# Power_12V_Rev1_1.net
KiCad netlist of a schematic drawn in Altium Designer
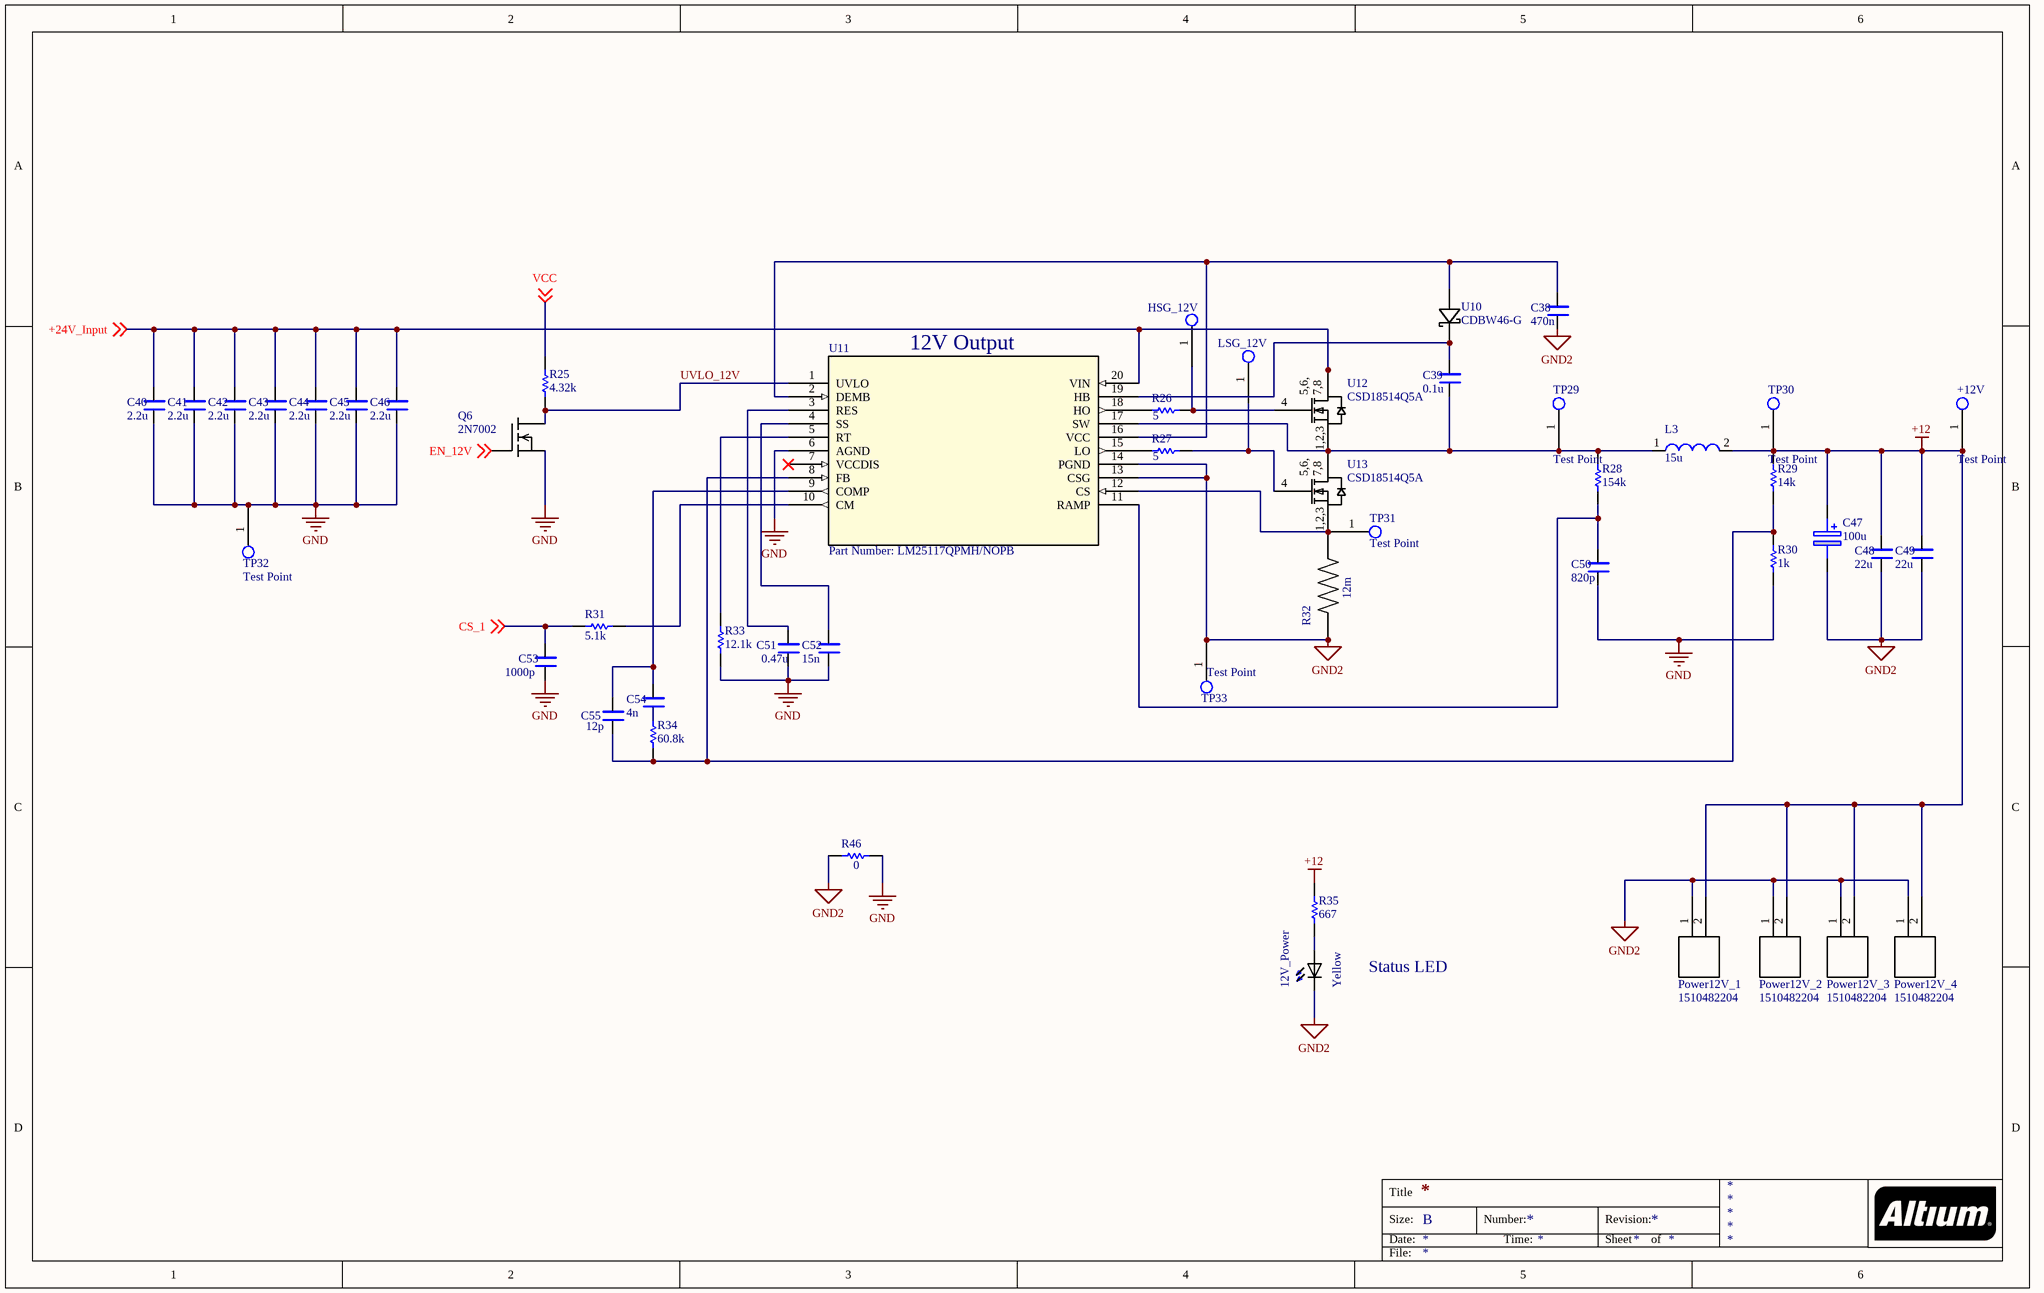
[diagram p0: Power_12V_Rev1.1.SchDoc]

(export (version "E")
  (design (tool "Eeschema 10.0.6"))
  (components
    (comp (ref "+12V")
      (value "Test Point")
      (footprint "Test Point Through-hole")
      (libsource (lib "Test Points") (part "Test Point"))
    )
    (comp (ref "12V_Power")
      (value "Yellow")
      (footprint "*DIOC200X125X110_LTST-C171KSKT(Primary)")
      (description "Yellow 2 x 1.25 x 0.8 mm 130Â° Water Clear 50 mcd 2 V LED SMT")
      (fields (field (name "MP") "LTST-C171KSKT") (field (name "DIGI-KEY_PART_NUMBER") "160-1428-1-ND"))
      (libsource (lib "LTST-C171KSKT") (part "LTST-C171KSKT"))
    )
    (comp (ref "C38")
      (value "470n")
      (footprint "*CAPC2012X88N")
      (description "100pF Â±5% 250V Ceramic Capacitor C0G, NP0 0805 _2012 Metric_")
      (fields (field (name "MF") "KEMET") (field (name "DIGI-KEY_PART_NUMBER") "399-15000-1-ND"))
      (libsource (lib "C0805C101JAGAC7800") (part "C0805C101JAGAC7800"))
    )
    (comp (ref "C39")
      (value "0.1u")
      (footprint "*CAPC2012X88N")
      (description "100pF Â±5% 250V Ceramic Capacitor C0G, NP0 0805 _2012 Metric_")
      (fields (field (name "MF") "KEMET") (field (name "DIGI-KEY_PART_NUMBER") "399-15000-1-ND"))
      (libsource (lib "C0805C101JAGAC7800") (part "C0805C101JAGAC7800"))
    )
    (comp (ref "C40")
      (value "2.2u")
      (footprint "*CAPC2012X88N")
      (description "100pF Â±5% 250V Ceramic Capacitor C0G, NP0 0805 _2012 Metric_")
      (fields (field (name "MF") "KEMET") (field (name "DIGI-KEY_PART_NUMBER") "399-15000-1-ND"))
      (libsource (lib "C0805C101JAGAC7800") (part "C0805C101JAGAC7800"))
    )
    (comp (ref "C41")
      (value "2.2u")
      (footprint "*CAPC2012X88N")
      (description "100pF Â±5% 250V Ceramic Capacitor C0G, NP0 0805 _2012 Metric_")
      (fields (field (name "MF") "KEMET") (field (name "DIGI-KEY_PART_NUMBER") "399-15000-1-ND"))
      (libsource (lib "C0805C101JAGAC7800") (part "C0805C101JAGAC7800"))
    )
    (comp (ref "C42")
      (value "2.2u")
      (footprint "*CAPC2012X88N")
      (description "100pF Â±5% 250V Ceramic Capacitor C0G, NP0 0805 _2012 Metric_")
      (fields (field (name "MF") "KEMET") (field (name "DIGI-KEY_PART_NUMBER") "399-15000-1-ND"))
      (libsource (lib "C0805C101JAGAC7800") (part "C0805C101JAGAC7800"))
    )
    (comp (ref "C43")
      (value "2.2u")
      (footprint "*CAPC2012X88N")
      (description "100pF Â±5% 250V Ceramic Capacitor C0G, NP0 0805 _2012 Metric_")
      (fields (field (name "MF") "KEMET") (field (name "DIGI-KEY_PART_NUMBER") "399-15000-1-ND"))
      (libsource (lib "C0805C101JAGAC7800") (part "C0805C101JAGAC7800"))
    )
    (comp (ref "C44")
      (value "2.2u")
      (footprint "*CAPC2012X88N")
      (description "100pF Â±5% 250V Ceramic Capacitor C0G, NP0 0805 _2012 Metric_")
      (fields (field (name "MF") "KEMET") (field (name "DIGI-KEY_PART_NUMBER") "399-15000-1-ND"))
      (libsource (lib "C0805C101JAGAC7800") (part "C0805C101JAGAC7800"))
    )
    (comp (ref "C45")
      (value "2.2u")
      (footprint "*CAPC2012X88N")
      (description "100pF Â±5% 250V Ceramic Capacitor C0G, NP0 0805 _2012 Metric_")
      (fields (field (name "MF") "KEMET") (field (name "DIGI-KEY_PART_NUMBER") "399-15000-1-ND"))
      (libsource (lib "C0805C101JAGAC7800") (part "C0805C101JAGAC7800"))
    )
    (comp (ref "C46")
      (value "2.2u")
      (footprint "*CAPC2012X88N")
      (description "100pF Â±5% 250V Ceramic Capacitor C0G, NP0 0805 _2012 Metric_")
      (fields (field (name "MF") "KEMET") (field (name "DIGI-KEY_PART_NUMBER") "399-15000-1-ND"))
      (libsource (lib "C0805C101JAGAC7800") (part "C0805C101JAGAC7800"))
    )
    (comp (ref "C47")
      (value "100u")
      (footprint "CAPPRD500W65D1000H1800")
      (fields
        (field (name "MANUFACTURER_PART_NUMBER") "EEUFC1V331")
        (field (name "RS PART NUMBER") "1081337")
      )
      (libsource (lib "Power Distribution") (part "EEUFC1V331"))
    )
    (comp (ref "C48")
      (value "22u")
      (footprint "*CAPC2012X88N")
      (description "100pF Â±5% 250V Ceramic Capacitor C0G, NP0 0805 _2012 Metric_")
      (fields (field (name "MF") "KEMET") (field (name "DIGI-KEY_PART_NUMBER") "399-15000-1-ND"))
      (libsource (lib "C0805C101JAGAC7800") (part "C0805C101JAGAC7800"))
    )
    (comp (ref "C49")
      (value "22u")
      (footprint "*CAPC2012X88N")
      (description "100pF Â±5% 250V Ceramic Capacitor C0G, NP0 0805 _2012 Metric_")
      (fields (field (name "MF") "KEMET") (field (name "DIGI-KEY_PART_NUMBER") "399-15000-1-ND"))
      (libsource (lib "C0805C101JAGAC7800") (part "C0805C101JAGAC7800"))
    )
    (comp (ref "C50")
      (value "820p")
      (footprint "*CAPC2012X88N")
      (description "100pF Â±5% 250V Ceramic Capacitor C0G, NP0 0805 _2012 Metric_")
      (fields (field (name "MF") "KEMET") (field (name "DIGI-KEY_PART_NUMBER") "399-15000-1-ND"))
      (libsource (lib "C0805C101JAGAC7800") (part "C0805C101JAGAC7800"))
    )
    (comp (ref "C51")
      (value "0.47u")
      (footprint "*CAPC2012X88N")
      (description "100pF Â±5% 250V Ceramic Capacitor C0G, NP0 0805 _2012 Metric_")
      (fields (field (name "MF") "KEMET") (field (name "DIGI-KEY_PART_NUMBER") "399-15000-1-ND"))
      (libsource (lib "C0805C101JAGAC7800") (part "C0805C101JAGAC7800"))
    )
    (comp (ref "C52")
      (value "15n")
      (footprint "*CAPC2012X88N")
      (description "100pF Â±5% 250V Ceramic Capacitor C0G, NP0 0805 _2012 Metric_")
      (fields (field (name "MF") "KEMET") (field (name "DIGI-KEY_PART_NUMBER") "399-15000-1-ND"))
      (libsource (lib "C0805C101JAGAC7800") (part "C0805C101JAGAC7800"))
    )
    (comp (ref "C53")
      (value "1000p")
      (footprint "*CAPC2012X88N")
      (description "100pF Â±5% 250V Ceramic Capacitor C0G, NP0 0805 _2012 Metric_")
      (fields (field (name "MF") "KEMET") (field (name "DIGI-KEY_PART_NUMBER") "399-15000-1-ND"))
      (libsource (lib "C0805C101JAGAC7800") (part "C0805C101JAGAC7800"))
    )
    (comp (ref "C54")
      (value "4n")
      (footprint "*CAPC2012X88N")
      (description "100pF Â±5% 250V Ceramic Capacitor C0G, NP0 0805 _2012 Metric_")
      (fields (field (name "MF") "KEMET") (field (name "DIGI-KEY_PART_NUMBER") "399-15000-1-ND"))
      (libsource (lib "C0805C101JAGAC7800") (part "C0805C101JAGAC7800"))
    )
    (comp (ref "C55")
      (value "12p")
      (footprint "*CAPC2012X88N")
      (description "100pF Â±5% 250V Ceramic Capacitor C0G, NP0 0805 _2012 Metric_")
      (fields (field (name "MF") "KEMET") (field (name "DIGI-KEY_PART_NUMBER") "399-15000-1-ND"))
      (libsource (lib "C0805C101JAGAC7800") (part "C0805C101JAGAC7800"))
    )
    (comp (ref "HSG_12V")
      (value "~")
      (footprint "Test Point Through-hole")
      (libsource (lib "Test Points") (part "Test Point"))
    )
    (comp (ref "L3")
      (value "15u")
      (footprint "XAL1010-682")
      (description "Power inductor, high current, 10% tol, SMT, RoHS")
      (fields (field (name "MF") "Coilcraft") (field (name "MP") "SER2915H-153KL"))
      (libsource (lib "SER2915H-153KL") (part "SER2915H-153KL"))
    )
    (comp (ref "LSG_12V")
      (value "~")
      (footprint "Test Point Through-hole")
      (libsource (lib "Test Points") (part "Test Point"))
    )
    (comp (ref "Power12V_1")
      (value "1510482204")
      (footprint "1510482204")
      (description "Molex 6.5MM 2 pin connector, used for power connections. P/N 1510482204 and similar models.")
      (libsource (lib "Power Distribution") (part "1510482204"))
    )
    (comp (ref "Power12V_2")
      (value "1510482204")
      (footprint "1510482204")
      (description "Molex 6.5MM 2 pin connector, used for power connections. P/N 1510482204 and similar models.")
      (libsource (lib "Power Distribution") (part "1510482204"))
    )
    (comp (ref "Power12V_3")
      (value "1510482204")
      (footprint "1510482204")
      (description "Molex 6.5MM 2 pin connector, used for power connections. P/N 1510482204 and similar models.")
      (libsource (lib "Power Distribution") (part "1510482204"))
    )
    (comp (ref "Power12V_4")
      (value "1510482204")
      (footprint "1510482204")
      (description "Molex 6.5MM 2 pin connector, used for power connections. P/N 1510482204 and similar models.")
      (libsource (lib "Power Distribution") (part "1510482204"))
    )
    (comp (ref "Q6")
      (value "2N7002")
      (footprint "*SOT23")
      (description "Trans MOSFET N-CH 60V 0.115A 3-Pin SOT-23 T/R")
      (fields (field (name "MF") "ON Semiconductor"))
      (libsource (lib "2N7002") (part "2N7002"))
    )
    (comp (ref "R25")
      (value "4.32k")
      (footprint "RESC0805(2012)_M")
      (description "8M06 0.125W 1% 0805 (2012 Metric)  SMD")
      (fields (field (name "POWER") "0.125 W") (field (name "TOLERANCE") "1 %"))
      (libsource (lib "Altium Content Vault") (part "RES"))
    )
    (comp (ref "R26")
      (value "5")
      (footprint "AXIAL-0.3")
      (description "120R 0.125W 5% 0805 (2012 Metric)  SMD")
      (fields (field (name "TOLERANCE") "5 %") (field (name "POWER") "0.125 W"))
      (libsource (lib "Power Distribution") (part "120R 5% 0805"))
    )
    (comp (ref "R27")
      (value "5")
      (footprint "AXIAL-0.3")
      (description "120R 0.125W 5% 0805 (2012 Metric)  SMD")
      (fields (field (name "TOLERANCE") "5 %") (field (name "POWER") "0.125 W"))
      (libsource (lib "Power Distribution") (part "120R 5% 0805"))
    )
    (comp (ref "R28")
      (value "154k")
      (footprint "RESC0805(2012)_M")
      (description "8M06 0.125W 1% 0805 (2012 Metric)  SMD")
      (fields (field (name "POWER") "0.125 W") (field (name "TOLERANCE") "1 %"))
      (libsource (lib "Altium Content Vault") (part "RES"))
    )
    (comp (ref "R29")
      (value "14k")
      (footprint "RESC0805(2012)_M")
      (description "8M06 0.125W 1% 0805 (2012 Metric)  SMD")
      (fields (field (name "POWER") "0.125 W") (field (name "TOLERANCE") "1 %"))
      (libsource (lib "Altium Content Vault") (part "RES"))
    )
    (comp (ref "R30")
      (value "1k")
      (footprint "RESC0805(2012)_M")
      (description "8M06 0.125W 1% 0805 (2012 Metric)  SMD")
      (fields (field (name "POWER") "0.125 W") (field (name "TOLERANCE") "1 %"))
      (libsource (lib "Altium Content Vault") (part "RES"))
    )
    (comp (ref "R31")
      (value "5.1k")
      (footprint "RESC0805(2012)_M")
      (description "8M06 0.125W 1% 0805 (2012 Metric)  SMD")
      (fields (field (name "POWER") "0.125 W") (field (name "TOLERANCE") "1 %"))
      (libsource (lib "Altium Content Vault") (part "RES"))
    )
    (comp (ref "R32")
      (value "12m")
      (footprint "*RESC6432X110N")
      (description "Res Thick Film 2512 0.012 Ohm 1% 1W Pad SMD Automotive T/R")
      (fields (field (name "MP") "ERJ-M1WSF12MU") (field (name "DIGI-KEY_PART_NUMBER") "P12MCT-ND"))
      (libsource (lib "ERJ-M1WSF12MU") (part "ERJ-M1WSF12MU"))
    )
    (comp (ref "R33")
      (value "12.1k")
      (footprint "RESC0805(2012)_M")
      (description "8M06 0.125W 1% 0805 (2012 Metric)  SMD")
      (fields (field (name "POWER") "0.125 W") (field (name "TOLERANCE") "1 %"))
      (libsource (lib "Altium Content Vault") (part "RES"))
    )
    (comp (ref "R34")
      (value "60.8k")
      (footprint "RESC0805(2012)_M")
      (description "8M06 0.125W 1% 0805 (2012 Metric)  SMD")
      (fields (field (name "POWER") "0.125 W") (field (name "TOLERANCE") "1 %"))
      (libsource (lib "Altium Content Vault") (part "RES"))
    )
    (comp (ref "R35")
      (value "667")
      (footprint "RESC0805(2012)_M")
      (description "8M06 0.125W 1% 0805 (2012 Metric)  SMD")
      (fields (field (name "POWER") "0.125 W") (field (name "TOLERANCE") "1 %"))
      (libsource (lib "Altium Content Vault") (part "RES"))
    )
    (comp (ref "R46")
      (value "0")
      (footprint "RESC0805(2012)_M")
      (description "8M06 0.125W 1% 0805 (2012 Metric)  SMD")
      (fields (field (name "POWER") "0.125 W") (field (name "TOLERANCE") "1 %"))
      (libsource (lib "Altium Content Vault") (part "RES"))
    )
    (comp (ref "TP29")
      (value "Test Point")
      (footprint "Test Point Through-hole")
      (libsource (lib "Test Points") (part "Test Point"))
    )
    (comp (ref "TP30")
      (value "Test Point")
      (footprint "Test Point Through-hole")
      (libsource (lib "Test Points") (part "Test Point"))
    )
    (comp (ref "TP31")
      (value "Test Point")
      (footprint "Test Point Through-hole")
      (libsource (lib "Test Points") (part "Test Point"))
    )
    (comp (ref "TP32")
      (value "Test Point")
      (footprint "Test Point Through-hole")
      (libsource (lib "Test Points") (part "Test Point"))
    )
    (comp (ref "TP33")
      (value "Test Point")
      (footprint "Test Point Through-hole")
      (libsource (lib "Test Points") (part "Test Point"))
    )
    (comp (ref "U10")
      (value "CDBW46-G")
      (footprint "CDBW")
      (description "No Description Available")
      (fields (field (name "COPYRIGHT") "Copyright (C) 2018 Accelerated Designs. All rights reserved"))
      (libsource (lib "DIODE SCHOTTKY 100V 150MA") (part "CDBW46-G"))
    )
    (comp (ref "U11")
      (value "Part Number: LM25117QPMH/NOPB")
      (footprint "MXA20A")
      (description "No Description Available")
      (fields
        (field (name "MANUFACTURER") "Texas Instruments")
        (field (name "MANUFACTURER_PART_NUMBER") "LM25117QPMH/NOPB")
        (field (name "COPYRIGHT") "Copyright (C) 2018 Accelerated Designs. All rights reserved")
      )
      (libsource (lib "2019-11-16_22-35-15") (part "LM25117QPMH/NOPB"))
    )
    (comp (ref "U12")
      (value "CSD18514Q5A")
      (footprint "DQJ0008A")
      (description "No Description Available")
      (fields (field (name "COPYRIGHT") "Copyright (C) 2018 Accelerated Designs. All rights reserved"))
      (libsource (lib "ul_CSD18514Q5A") (part "CSD18514Q5A"))
    )
    (comp (ref "U13")
      (value "CSD18514Q5A")
      (footprint "DQJ0008A")
      (description "No Description Available")
      (fields (field (name "COPYRIGHT") "Copyright (C) 2018 Accelerated Designs. All rights reserved"))
      (libsource (lib "ul_CSD18514Q5A") (part "CSD18514Q5A"))
    )
  )
  (nets
    (net (code "1") (name "+12") (class "Default")
      (node (ref "+12V") (pin "1") (pinfunction "1_1") (pintype "passive"))
      (node (ref "C47") (pin "1") (pinfunction "+_1") (pintype "passive"))
      (node (ref "C48") (pin "2") (pinfunction "2_2") (pintype "passive"))
      (node (ref "C49") (pin "2") (pinfunction "2_2") (pintype "passive"))
      (node (ref "L3") (pin "2") (pinfunction "2_2") (pintype "passive"))
      (node (ref "Power12V_1") (pin "2") (pintype "passive"))
      (node (ref "Power12V_2") (pin "2") (pintype "passive"))
      (node (ref "Power12V_3") (pin "2") (pintype "passive"))
      (node (ref "Power12V_4") (pin "2") (pintype "passive"))
      (node (ref "R29") (pin "2") (pinfunction "2_2") (pintype "passive"))
      (node (ref "R35") (pin "2") (pinfunction "2_2") (pintype "passive"))
      (node (ref "TP30") (pin "1") (pinfunction "1_1") (pintype "passive"))
    )
    (net (code "2") (name "+24V_Input") (class "Default")
      (node (ref "C40") (pin "2") (pinfunction "2_2") (pintype "passive"))
      (node (ref "C41") (pin "2") (pinfunction "2_2") (pintype "passive"))
      (node (ref "C42") (pin "2") (pinfunction "2_2") (pintype "passive"))
      (node (ref "C43") (pin "2") (pinfunction "2_2") (pintype "passive"))
      (node (ref "C44") (pin "2") (pinfunction "2_2") (pintype "passive"))
      (node (ref "C45") (pin "2") (pinfunction "2_2") (pintype "passive"))
      (node (ref "C46") (pin "2") (pinfunction "2_2") (pintype "passive"))
      (node (ref "U11") (pin "20") (pinfunction "VIN_20") (pintype "input"))
      (node (ref "U12") (pin "5") (pinfunction "D_5") (pintype "passive"))
      (node (ref "U12") (pin "6") (pinfunction "D_6") (pintype "passive"))
      (node (ref "U12") (pin "7") (pinfunction "D_7") (pintype "passive"))
      (node (ref "U12") (pin "8") (pinfunction "D_8") (pintype "passive"))
    )
    (net (code "3") (name "/UVLO_12V") (class "Default")
      (node (ref "Q6") (pin "3") (pinfunction "D_3") (pintype "passive"))
      (node (ref "R25") (pin "1") (pinfunction "1_1") (pintype "passive"))
      (node (ref "U11") (pin "1") (pinfunction "UVLO_1") (pintype "passive"))
    )
    (net (code "4") (name "CS_1") (class "Default")
      (node (ref "C53") (pin "2") (pinfunction "2_2") (pintype "passive"))
      (node (ref "R31") (pin "2") (pinfunction "2_2") (pintype "passive"))
    )
    (net (code "5") (name "EN_12V") (class "Default")
      (node (ref "Q6") (pin "1") (pinfunction "G_1") (pintype "passive"))
    )
    (net (code "6") (name "GND") (class "Default")
      (node (ref "C40") (pin "1") (pinfunction "1_1") (pintype "passive"))
      (node (ref "C41") (pin "1") (pinfunction "1_1") (pintype "passive"))
      (node (ref "C42") (pin "1") (pinfunction "1_1") (pintype "passive"))
      (node (ref "C43") (pin "1") (pinfunction "1_1") (pintype "passive"))
      (node (ref "C44") (pin "1") (pinfunction "1_1") (pintype "passive"))
      (node (ref "C45") (pin "1") (pinfunction "1_1") (pintype "passive"))
      (node (ref "C46") (pin "1") (pinfunction "1_1") (pintype "passive"))
      (node (ref "C50") (pin "1") (pinfunction "1_1") (pintype "passive"))
      (node (ref "C51") (pin "1") (pinfunction "1_1") (pintype "passive"))
      (node (ref "C52") (pin "1") (pinfunction "1_1") (pintype "passive"))
      (node (ref "C53") (pin "1") (pinfunction "1_1") (pintype "passive"))
      (node (ref "Q6") (pin "2") (pinfunction "S_2") (pintype "passive"))
      (node (ref "R30") (pin "1") (pinfunction "1_1") (pintype "passive"))
      (node (ref "R33") (pin "1") (pinfunction "1_1") (pintype "passive"))
      (node (ref "R46") (pin "1") (pinfunction "1_1") (pintype "passive"))
      (node (ref "TP32") (pin "1") (pinfunction "1_1") (pintype "passive"))
      (node (ref "U11") (pin "6") (pinfunction "AGND_6") (pintype "power_in"))
    )
    (net (code "7") (name "GND2") (class "Default")
      (node (ref "12V_Power") (pin "NEG") (pinfunction "NEG_NEG") (pintype "passive"))
      (node (ref "C38") (pin "1") (pinfunction "1_1") (pintype "passive"))
      (node (ref "C47") (pin "2") (pinfunction "-_2") (pintype "passive"))
      (node (ref "C48") (pin "1") (pinfunction "1_1") (pintype "passive"))
      (node (ref "C49") (pin "1") (pinfunction "1_1") (pintype "passive"))
      (node (ref "Power12V_1") (pin "1") (pintype "passive"))
      (node (ref "Power12V_2") (pin "1") (pintype "passive"))
      (node (ref "Power12V_3") (pin "1") (pintype "passive"))
      (node (ref "Power12V_4") (pin "1") (pintype "passive"))
      (node (ref "R32") (pin "1") (pinfunction "1_1") (pintype "passive"))
      (node (ref "R46") (pin "2") (pinfunction "2_2") (pintype "passive"))
      (node (ref "TP33") (pin "1") (pinfunction "1_1") (pintype "passive"))
      (node (ref "U11") (pin "13") (pinfunction "CSG_13") (pintype "passive"))
      (node (ref "U11") (pin "14") (pinfunction "PGND_14") (pintype "power_in"))
    )
    (net (code "8") (name "Net-(12V_Power-PadPOS)") (class "Default")
      (node (ref "12V_Power") (pin "POS") (pinfunction "POS_POS") (pintype "passive"))
      (node (ref "R35") (pin "1") (pinfunction "1_1") (pintype "passive"))
    )
    (net (code "9") (name "Net-(C54-Pad1)") (class "Default")
      (node (ref "C54") (pin "1") (pinfunction "1_1") (pintype "passive"))
      (node (ref "R34") (pin "2") (pinfunction "2_2") (pintype "passive"))
    )
    (net (code "10") (name "Net-(U11-CM)") (class "Default")
      (node (ref "R31") (pin "1") (pinfunction "1_1") (pintype "passive"))
      (node (ref "U11") (pin "10") (pinfunction "CM_10") (pintype "output"))
    )
    (net (code "11") (name "Net-(U11-COMP)") (class "Default")
      (node (ref "C54") (pin "2") (pinfunction "2_2") (pintype "passive"))
      (node (ref "C55") (pin "2") (pinfunction "2_2") (pintype "passive"))
      (node (ref "U11") (pin "9") (pinfunction "COMP_9") (pintype "output"))
    )
    (net (code "12") (name "Net-(U11-CS)") (class "Default")
      (node (ref "R32") (pin "2") (pinfunction "2_2") (pintype "passive"))
      (node (ref "TP31") (pin "1") (pinfunction "1_1") (pintype "passive"))
      (node (ref "U11") (pin "12") (pinfunction "CS_12") (pintype "input"))
      (node (ref "U13") (pin "1") (pinfunction "S_1") (pintype "passive"))
      (node (ref "U13") (pin "2") (pinfunction "S_2") (pintype "passive"))
      (node (ref "U13") (pin "3") (pinfunction "S_3") (pintype "passive"))
    )
    (net (code "13") (name "Net-(U11-DEMB)") (class "Default")
      (node (ref "C38") (pin "2") (pinfunction "2_2") (pintype "passive"))
      (node (ref "U10") (pin "2") (pinfunction "2_2") (pintype "passive"))
      (node (ref "U11") (pin "16") (pinfunction "VCC_16") (pintype "power_in"))
      (node (ref "U11") (pin "2") (pinfunction "DEMB_2") (pintype "input"))
    )
    (net (code "14") (name "Net-(U11-FB)") (class "Default")
      (node (ref "C55") (pin "1") (pinfunction "1_1") (pintype "passive"))
      (node (ref "R29") (pin "1") (pinfunction "1_1") (pintype "passive"))
      (node (ref "R30") (pin "2") (pinfunction "2_2") (pintype "passive"))
      (node (ref "R34") (pin "1") (pinfunction "1_1") (pintype "passive"))
      (node (ref "U11") (pin "8") (pinfunction "FB_8") (pintype "input"))
    )
    (net (code "15") (name "Net-(U11-HB)") (class "Default")
      (node (ref "C39") (pin "2") (pinfunction "2_2") (pintype "passive"))
      (node (ref "U10") (pin "1") (pinfunction "1_1") (pintype "passive"))
      (node (ref "U11") (pin "19") (pinfunction "HB_19") (pintype "passive"))
    )
    (net (code "16") (name "Net-(U11-HO)") (class "Default")
      (node (ref "R26") (pin "1") (pinfunction "1_1") (pintype "passive"))
      (node (ref "U11") (pin "18") (pinfunction "HO_18") (pintype "output"))
    )
    (net (code "17") (name "Net-(U11-LO)") (class "Default")
      (node (ref "R27") (pin "1") (pinfunction "1_1") (pintype "passive"))
      (node (ref "U11") (pin "15") (pinfunction "LO_15") (pintype "output"))
    )
    (net (code "18") (name "Net-(U11-RAMP)") (class "Default")
      (node (ref "C50") (pin "2") (pinfunction "2_2") (pintype "passive"))
      (node (ref "R28") (pin "1") (pinfunction "1_1") (pintype "passive"))
      (node (ref "U11") (pin "11") (pinfunction "RAMP_11") (pintype "passive"))
    )
    (net (code "19") (name "Net-(U11-RES)") (class "Default")
      (node (ref "C51") (pin "2") (pinfunction "2_2") (pintype "passive"))
      (node (ref "U11") (pin "3") (pinfunction "RES_3") (pintype "passive"))
    )
    (net (code "20") (name "Net-(U11-RT)") (class "Default")
      (node (ref "R33") (pin "2") (pinfunction "2_2") (pintype "passive"))
      (node (ref "U11") (pin "5") (pinfunction "RT_5") (pintype "passive"))
    )
    (net (code "21") (name "Net-(U11-SS)") (class "Default")
      (node (ref "C52") (pin "2") (pinfunction "2_2") (pintype "passive"))
      (node (ref "U11") (pin "4") (pinfunction "SS_4") (pintype "passive"))
    )
    (net (code "22") (name "Net-(U11-SW)") (class "Default")
      (node (ref "C39") (pin "1") (pinfunction "1_1") (pintype "passive"))
      (node (ref "L3") (pin "1") (pinfunction "1_1") (pintype "passive"))
      (node (ref "R28") (pin "2") (pinfunction "2_2") (pintype "passive"))
      (node (ref "TP29") (pin "1") (pinfunction "1_1") (pintype "passive"))
      (node (ref "U11") (pin "17") (pinfunction "SW_17") (pintype "passive"))
      (node (ref "U12") (pin "1") (pinfunction "S_1") (pintype "passive"))
      (node (ref "U12") (pin "2") (pinfunction "S_2") (pintype "passive"))
      (node (ref "U12") (pin "3") (pinfunction "S_3") (pintype "passive"))
      (node (ref "U13") (pin "5") (pinfunction "D_5") (pintype "passive"))
      (node (ref "U13") (pin "6") (pinfunction "D_6") (pintype "passive"))
      (node (ref "U13") (pin "7") (pinfunction "D_7") (pintype "passive"))
      (node (ref "U13") (pin "8") (pinfunction "D_8") (pintype "passive"))
    )
    (net (code "23") (name "Net-(U12-G)") (class "Default")
      (node (ref "HSG_12V") (pin "1") (pinfunction "1_1") (pintype "passive"))
      (node (ref "R26") (pin "2") (pinfunction "2_2") (pintype "passive"))
      (node (ref "U12") (pin "4") (pinfunction "G_4") (pintype "passive"))
    )
    (net (code "24") (name "Net-(U13-G)") (class "Default")
      (node (ref "LSG_12V") (pin "1") (pinfunction "1_1") (pintype "passive"))
      (node (ref "R27") (pin "2") (pinfunction "2_2") (pintype "passive"))
      (node (ref "U13") (pin "4") (pinfunction "G_4") (pintype "passive"))
    )
    (net (code "25") (name "VCC") (class "Default")
      (node (ref "R25") (pin "2") (pinfunction "2_2") (pintype "passive"))
    )
    (net (code "26") (name "unconnected-(U11-VCCDIS-Pad7)") (class "Default")
      (node (ref "U11") (pin "7") (pinfunction "VCCDIS_7") (pintype "input+no_connect"))
    )
  )
)
